# W5500_SCH.net
KiCad netlist of a schematic drawn in Altium Designer
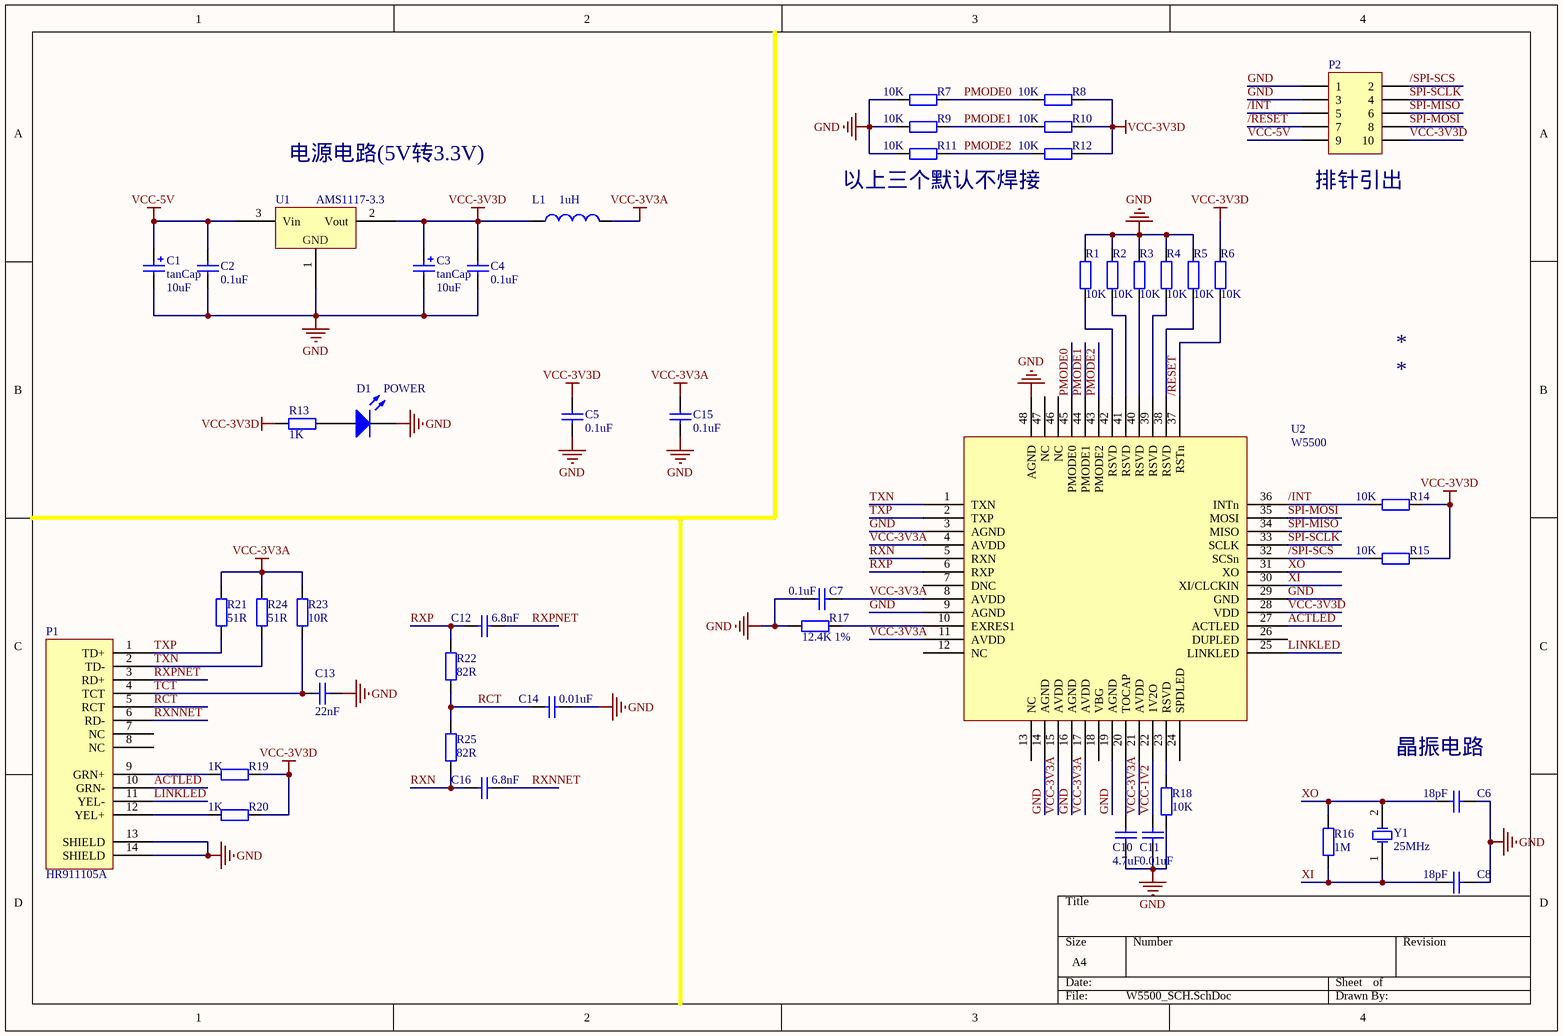
[diagram p0: W5500_SCH.SchDoc]

(export (version "E")
  (design (tool "Eeschema 10.0.6"))
  (components
    (comp (ref "C1")
      (value "tanCap")
      (footprint "C1206")
      (description "Polarized Capacitor (Axial)")
      (fields (field (name "ALTIUM_VALUE") "10uF") (field (name "PUBLISHER") "Altium Limited"))
      (libsource (lib "Miscellaneous Devices") (part "Cap Pol2"))
    )
    (comp (ref "C2")
      (value "0.1uF")
      (footprint "C0805")
      (description "Capacitor")
      (fields (field (name "Comment") "Cap") (field (name "PUBLISHER") "Altium Limited"))
      (libsource (lib "Miscellaneous Devices") (part "Cap"))
    )
    (comp (ref "C3")
      (value "tanCap")
      (footprint "C1206")
      (description "Polarized Capacitor (Axial)")
      (fields (field (name "ALTIUM_VALUE") "10uF") (field (name "PUBLISHER") "Altium Limited"))
      (libsource (lib "Miscellaneous Devices") (part "Cap Pol2"))
    )
    (comp (ref "C4")
      (value "0.1uF")
      (footprint "C0805")
      (description "Capacitor")
      (fields (field (name "Comment") "Cap") (field (name "PUBLISHER") "Altium Limited"))
      (libsource (lib "Miscellaneous Devices") (part "Cap"))
    )
    (comp (ref "C5")
      (value "0.1uF")
      (footprint "C0805")
      (description "Capacitor")
      (fields (field (name "Comment") "Cap") (field (name "PUBLISHER") "Altium Limited"))
      (libsource (lib "Miscellaneous Devices") (part "Cap"))
    )
    (comp (ref "C6")
      (value "18pF")
      (footprint "C0805")
      (description "Capacitor")
      (fields (field (name "Comment") "Cap") (field (name "PUBLISHER") "Altium Limited"))
      (libsource (lib "Miscellaneous Devices") (part "Cap"))
    )
    (comp (ref "C7")
      (value "0.1uF")
      (footprint "C0805")
      (description "Capacitor")
      (fields (field (name "Comment") "Cap") (field (name "PUBLISHER") "Altium Limited"))
      (libsource (lib "Miscellaneous Devices") (part "Cap"))
    )
    (comp (ref "C8")
      (value "18pF")
      (footprint "C0805")
      (description "Capacitor")
      (fields (field (name "Comment") "Cap") (field (name "PUBLISHER") "Altium Limited"))
      (libsource (lib "Miscellaneous Devices") (part "Cap"))
    )
    (comp (ref "C10")
      (value "4.7uF")
      (footprint "C0805")
      (description "Capacitor")
      (fields (field (name "Comment") "Cap") (field (name "PUBLISHER") "Altium Limited"))
      (libsource (lib "Miscellaneous Devices") (part "Cap"))
    )
    (comp (ref "C11")
      (value "0.01uF")
      (footprint "C0805")
      (description "Capacitor")
      (fields (field (name "Comment") "Cap") (field (name "PUBLISHER") "Altium Limited"))
      (libsource (lib "Miscellaneous Devices") (part "Cap"))
    )
    (comp (ref "C12")
      (value "6.8nF")
      (footprint "C0805")
      (description "Capacitor")
      (fields (field (name "Comment") "Cap") (field (name "PUBLISHER") "Altium Limited"))
      (libsource (lib "Miscellaneous Devices") (part "Cap"))
    )
    (comp (ref "C13")
      (value "22nF")
      (footprint "C0805")
      (description "Capacitor")
      (fields (field (name "Comment") "Cap") (field (name "PUBLISHER") "Altium Limited"))
      (libsource (lib "Miscellaneous Devices") (part "Cap"))
    )
    (comp (ref "C14")
      (value "0.01uF")
      (footprint "C0805")
      (description "Capacitor")
      (fields (field (name "Comment") "Cap") (field (name "PUBLISHER") "Altium Limited"))
      (libsource (lib "Miscellaneous Devices") (part "Cap"))
    )
    (comp (ref "C15")
      (value "0.1uF")
      (footprint "C0805")
      (description "Capacitor")
      (fields (field (name "Comment") "Cap") (field (name "PUBLISHER") "Altium Limited"))
      (libsource (lib "Miscellaneous Devices") (part "Cap"))
    )
    (comp (ref "C16")
      (value "6.8nF")
      (footprint "C0805")
      (description "Capacitor")
      (fields (field (name "Comment") "Cap") (field (name "PUBLISHER") "Altium Limited"))
      (libsource (lib "Miscellaneous Devices") (part "Cap"))
    )
    (comp (ref "D1")
      (value "POWER")
      (footprint "C0805")
      (description "Typical INFRARED GaAs LED")
      (fields (field (name "PUBLISHER") "Altium Limited"))
      (libsource (lib "Miscellaneous Devices") (part "LED0"))
    )
    (comp (ref "L1")
      (value "1uH")
      (footprint "C0805")
      (description "Inductor")
      (fields (field (name "PUBLISHER") "Altium Limited"))
      (libsource (lib "Miscellaneous Devices") (part "Inductor"))
    )
    (comp (ref "P1")
      (value "HR911105A")
      (footprint "HR911105A")
      (description "RJ45插座")
      (libsource (lib "W5500_SCH") (part "HR911105A"))
    )
    (comp (ref "P2")
      (value "排针引出")
      (footprint "HDR2X5")
      (description "Header, 5-Pin, Dual row")
      (fields (field (name "PUBLISHER") "Altium Limited"))
      (libsource (lib "Miscellaneous Connectors") (part "Header 5X2"))
    )
    (comp (ref "R1")
      (value "10K")
      (footprint "C0805")
      (description "Resistor")
      (fields (field (name "Comment") "Res2") (field (name "PUBLISHER") "Altium Limited"))
      (libsource (lib "Miscellaneous Devices") (part "Res2"))
    )
    (comp (ref "R2")
      (value "10K")
      (footprint "C0805")
      (description "Resistor")
      (fields (field (name "Comment") "Res2") (field (name "PUBLISHER") "Altium Limited"))
      (libsource (lib "Miscellaneous Devices") (part "Res2"))
    )
    (comp (ref "R3")
      (value "10K")
      (footprint "C0805")
      (description "Resistor")
      (fields (field (name "Comment") "Res2") (field (name "PUBLISHER") "Altium Limited"))
      (libsource (lib "Miscellaneous Devices") (part "Res2"))
    )
    (comp (ref "R4")
      (value "10K")
      (footprint "C0805")
      (description "Resistor")
      (fields (field (name "Comment") "Res2") (field (name "PUBLISHER") "Altium Limited"))
      (libsource (lib "Miscellaneous Devices") (part "Res2"))
    )
    (comp (ref "R5")
      (value "10K")
      (footprint "C0805")
      (description "Resistor")
      (fields (field (name "Comment") "Res2") (field (name "PUBLISHER") "Altium Limited"))
      (libsource (lib "Miscellaneous Devices") (part "Res2"))
    )
    (comp (ref "R6")
      (value "10K")
      (footprint "C0805")
      (description "Resistor")
      (fields (field (name "Comment") "Res2") (field (name "PUBLISHER") "Altium Limited"))
      (libsource (lib "Miscellaneous Devices") (part "Res2"))
    )
    (comp (ref "R7")
      (value "10K")
      (footprint "C0805")
      (description "Resistor")
      (fields (field (name "Comment") "Res2") (field (name "PUBLISHER") "Altium Limited"))
      (libsource (lib "") (part "Res2_1"))
    )
    (comp (ref "R8")
      (value "10K")
      (footprint "C0805")
      (description "Resistor")
      (fields (field (name "Comment") "Res2") (field (name "PUBLISHER") "Altium Limited"))
      (libsource (lib "") (part "Res2_1"))
    )
    (comp (ref "R9")
      (value "10K")
      (footprint "C0805")
      (description "Resistor")
      (fields (field (name "Comment") "Res2") (field (name "PUBLISHER") "Altium Limited"))
      (libsource (lib "") (part "Res2_1"))
    )
    (comp (ref "R10")
      (value "10K")
      (footprint "C0805")
      (description "Resistor")
      (fields (field (name "Comment") "Res2") (field (name "PUBLISHER") "Altium Limited"))
      (libsource (lib "") (part "Res2_1"))
    )
    (comp (ref "R11")
      (value "10K")
      (footprint "C0805")
      (description "Resistor")
      (fields (field (name "Comment") "Res2") (field (name "PUBLISHER") "Altium Limited"))
      (libsource (lib "") (part "Res2_1"))
    )
    (comp (ref "R12")
      (value "10K")
      (footprint "C0805")
      (description "Resistor")
      (fields (field (name "Comment") "Res2") (field (name "PUBLISHER") "Altium Limited"))
      (libsource (lib "") (part "Res2_1"))
    )
    (comp (ref "R13")
      (value "1K")
      (footprint "C0805")
      (description "Resistor")
      (fields (field (name "Comment") "Res2") (field (name "PUBLISHER") "Altium Limited"))
      (libsource (lib "") (part "Res2_2"))
    )
    (comp (ref "R14")
      (value "10K")
      (footprint "C0805")
      (description "Resistor")
      (fields (field (name "Comment") "Res2") (field (name "PUBLISHER") "Altium Limited"))
      (libsource (lib "") (part "Res2_1"))
    )
    (comp (ref "R15")
      (value "10K")
      (footprint "C0805")
      (description "Resistor")
      (fields (field (name "Comment") "Res2") (field (name "PUBLISHER") "Altium Limited"))
      (libsource (lib "") (part "Res2_1"))
    )
    (comp (ref "R16")
      (value "1M")
      (footprint "C0805")
      (description "Resistor")
      (fields (field (name "Comment") "Res2") (field (name "PUBLISHER") "Altium Limited"))
      (libsource (lib "Miscellaneous Devices") (part "Res2"))
    )
    (comp (ref "R17")
      (value "12.4K 1%")
      (footprint "C0805")
      (description "Resistor")
      (fields (field (name "Comment") "Res2") (field (name "PUBLISHER") "Altium Limited"))
      (libsource (lib "") (part "Res2_1"))
    )
    (comp (ref "R18")
      (value "10K")
      (footprint "C0805")
      (description "Resistor")
      (fields (field (name "Comment") "Res2") (field (name "PUBLISHER") "Altium Limited"))
      (libsource (lib "Miscellaneous Devices") (part "Res2"))
    )
    (comp (ref "R19")
      (value "1K")
      (footprint "C0805")
      (description "Resistor")
      (fields (field (name "Comment") "Res2") (field (name "PUBLISHER") "Altium Limited"))
      (libsource (lib "") (part "Res2_2"))
    )
    (comp (ref "R20")
      (value "1K")
      (footprint "C0805")
      (description "Resistor")
      (fields (field (name "Comment") "Res2") (field (name "PUBLISHER") "Altium Limited"))
      (libsource (lib "") (part "Res2_2"))
    )
    (comp (ref "R21")
      (value "51R")
      (footprint "C0805")
      (description "Resistor")
      (fields (field (name "Comment") "Res2") (field (name "PUBLISHER") "Altium Limited"))
      (libsource (lib "") (part "Res2_3"))
    )
    (comp (ref "R22")
      (value "82R")
      (footprint "C0805")
      (description "Resistor")
      (fields (field (name "Comment") "Res2") (field (name "PUBLISHER") "Altium Limited"))
      (libsource (lib "Miscellaneous Devices") (part "Res2"))
    )
    (comp (ref "R23")
      (value "10R")
      (footprint "C0805")
      (description "Resistor")
      (fields (field (name "Comment") "Res2") (field (name "PUBLISHER") "Altium Limited"))
      (libsource (lib "") (part "Res2_3"))
    )
    (comp (ref "R24")
      (value "51R")
      (footprint "C0805")
      (description "Resistor")
      (fields (field (name "Comment") "Res2") (field (name "PUBLISHER") "Altium Limited"))
      (libsource (lib "") (part "Res2_3"))
    )
    (comp (ref "R25")
      (value "82R")
      (footprint "C0805")
      (description "Resistor")
      (fields (field (name "Comment") "Res2") (field (name "PUBLISHER") "Altium Limited"))
      (libsource (lib "Miscellaneous Devices") (part "Res2"))
    )
    (comp (ref "U1")
      (value "AMS1117-3.3")
      (footprint "SOT223_M")
      (description "AMS1117-")
      (libsource (lib "qyh") (part "AMS1117"))
    )
    (comp (ref "U2")
      (value "W5500")
      (footprint "LQFP48")
      (description "W5500以太网芯片")
      (libsource (lib "W5500_SCH") (part "W5500"))
    )
    (comp (ref "Y1")
      (value "25MHz")
      (footprint "XTAL-HC49")
      (description "Crystal Oscillator")
      (fields (field (name "PUBLISHER") "Altium Limited"))
      (libsource (lib "Miscellaneous Devices") (part "XTAL"))
    )
  )
  (nets
    (net (code "1") (name "/ACTLED") (class "Default")
      (node (ref "P1") (pin "10") (pinfunction "GRN-_10") (pintype "passive"))
      (node (ref "U2") (pin "27") (pinfunction "ACTLED_27") (pintype "passive"))
    )
    (net (code "2") (name "/LINKLED") (class "Default")
      (node (ref "P1") (pin "11") (pinfunction "YEL-_11") (pintype "passive"))
      (node (ref "U2") (pin "25") (pinfunction "LINKLED_25") (pintype "passive"))
    )
    (net (code "3") (name "/PMODE0") (class "Default")
      (node (ref "R7") (pin "2") (pinfunction "2_2") (pintype "passive"))
      (node (ref "R8") (pin "1") (pinfunction "1_1") (pintype "passive"))
      (node (ref "U2") (pin "45") (pinfunction "PMODE0_45") (pintype "passive"))
    )
    (net (code "4") (name "/PMODE1") (class "Default")
      (node (ref "R10") (pin "1") (pinfunction "1_1") (pintype "passive"))
      (node (ref "R9") (pin "2") (pinfunction "2_2") (pintype "passive"))
      (node (ref "U2") (pin "44") (pinfunction "PMODE1_44") (pintype "passive"))
    )
    (net (code "5") (name "/PMODE2") (class "Default")
      (node (ref "R11") (pin "2") (pinfunction "2_2") (pintype "passive"))
      (node (ref "R12") (pin "1") (pinfunction "1_1") (pintype "passive"))
      (node (ref "U2") (pin "43") (pinfunction "PMODE2_43") (pintype "passive"))
    )
    (net (code "6") (name "/RCT") (class "Default")
      (node (ref "C14") (pin "2") (pinfunction "2_2") (pintype "passive"))
      (node (ref "P1") (pin "5") (pinfunction "RCT_5") (pintype "passive"))
      (node (ref "R22") (pin "1") (pinfunction "1_1") (pintype "passive"))
      (node (ref "R25") (pin "2") (pinfunction "2_2") (pintype "passive"))
    )
    (net (code "7") (name "/RXN") (class "Default")
      (node (ref "C16") (pin "2") (pinfunction "2_2") (pintype "passive"))
      (node (ref "R25") (pin "1") (pinfunction "1_1") (pintype "passive"))
      (node (ref "U2") (pin "5") (pinfunction "RXN_5") (pintype "passive"))
    )
    (net (code "8") (name "/RXNNET") (class "Default")
      (node (ref "C16") (pin "1") (pinfunction "1_1") (pintype "passive"))
      (node (ref "P1") (pin "6") (pinfunction "RD-_6") (pintype "passive"))
    )
    (net (code "9") (name "/RXP") (class "Default")
      (node (ref "C12") (pin "2") (pinfunction "2_2") (pintype "passive"))
      (node (ref "R22") (pin "2") (pinfunction "2_2") (pintype "passive"))
      (node (ref "U2") (pin "6") (pinfunction "RXP_6") (pintype "passive"))
    )
    (net (code "10") (name "/RXPNET") (class "Default")
      (node (ref "C12") (pin "1") (pinfunction "1_1") (pintype "passive"))
      (node (ref "P1") (pin "3") (pinfunction "RD+_3") (pintype "passive"))
    )
    (net (code "11") (name "/SPI-MISO") (class "Default")
      (node (ref "P2") (pin "6") (pinfunction "6_6") (pintype "passive"))
      (node (ref "U2") (pin "34") (pinfunction "MISO_34") (pintype "passive"))
    )
    (net (code "12") (name "/SPI-MOSI") (class "Default")
      (node (ref "P2") (pin "8") (pinfunction "8_8") (pintype "passive"))
      (node (ref "U2") (pin "35") (pinfunction "MOSI_35") (pintype "passive"))
    )
    (net (code "13") (name "/SPI-SCLK") (class "Default")
      (node (ref "P2") (pin "4") (pinfunction "4_4") (pintype "passive"))
      (node (ref "U2") (pin "33") (pinfunction "SCLK_33") (pintype "passive"))
    )
    (net (code "14") (name "/TCT") (class "Default")
      (node (ref "C13") (pin "1") (pinfunction "1_1") (pintype "passive"))
      (node (ref "P1") (pin "4") (pinfunction "TCT_4") (pintype "passive"))
      (node (ref "R23") (pin "2") (pinfunction "2_2") (pintype "passive"))
    )
    (net (code "15") (name "/TXN") (class "Default")
      (node (ref "P1") (pin "2") (pinfunction "TD-_2") (pintype "passive"))
      (node (ref "R24") (pin "2") (pinfunction "2_2") (pintype "passive"))
      (node (ref "U2") (pin "1") (pinfunction "TXN_1") (pintype "passive"))
    )
    (net (code "16") (name "/TXP") (class "Default")
      (node (ref "P1") (pin "1") (pinfunction "TD+_1") (pintype "passive"))
      (node (ref "R21") (pin "2") (pinfunction "2_2") (pintype "passive"))
      (node (ref "U2") (pin "2") (pinfunction "TXP_2") (pintype "passive"))
    )
    (net (code "17") (name "/VCC-1V2") (class "Default")
      (node (ref "C11") (pin "1") (pinfunction "1_1") (pintype "passive"))
      (node (ref "U2") (pin "22") (pinfunction "1V2O_22") (pintype "passive"))
    )
    (net (code "18") (name "/XI") (class "Default")
      (node (ref "C8") (pin "2") (pinfunction "2_2") (pintype "passive"))
      (node (ref "R16") (pin "1") (pinfunction "1_1") (pintype "passive"))
      (node (ref "U2") (pin "30") (pinfunction "XI/CLCKIN_30") (pintype "passive"))
      (node (ref "Y1") (pin "1") (pinfunction "OSC1_1") (pintype "passive"))
    )
    (net (code "19") (name "/XO") (class "Default")
      (node (ref "C6") (pin "2") (pinfunction "2_2") (pintype "passive"))
      (node (ref "R16") (pin "2") (pinfunction "2_2") (pintype "passive"))
      (node (ref "U2") (pin "31") (pinfunction "XO_31") (pintype "passive"))
      (node (ref "Y1") (pin "2") (pinfunction "OSC2_2") (pintype "passive"))
    )
    (net (code "20") (name "/{slash}INT") (class "Default")
      (node (ref "P2") (pin "5") (pinfunction "5_5") (pintype "passive"))
      (node (ref "R14") (pin "1") (pinfunction "1_1") (pintype "passive"))
      (node (ref "U2") (pin "36") (pinfunction "INTn_36") (pintype "passive"))
    )
    (net (code "21") (name "/{slash}RESET") (class "Default")
      (node (ref "P2") (pin "7") (pinfunction "7_7") (pintype "passive"))
      (node (ref "R6") (pin "1") (pinfunction "1_1") (pintype "passive"))
      (node (ref "U2") (pin "37") (pinfunction "RSTn_37") (pintype "passive"))
    )
    (net (code "22") (name "/{slash}SPI-SCS") (class "Default")
      (node (ref "P2") (pin "2") (pinfunction "2_2") (pintype "passive"))
      (node (ref "R15") (pin "1") (pinfunction "1_1") (pintype "passive"))
      (node (ref "U2") (pin "32") (pinfunction "SCSn_32") (pintype "passive"))
    )
    (net (code "23") (name "GND") (class "Default")
      (node (ref "C1") (pin "2") (pinfunction "2_2") (pintype "passive"))
      (node (ref "C10") (pin "2") (pinfunction "2_2") (pintype "passive"))
      (node (ref "C11") (pin "2") (pinfunction "2_2") (pintype "passive"))
      (node (ref "C13") (pin "2") (pinfunction "2_2") (pintype "passive"))
      (node (ref "C14") (pin "1") (pinfunction "1_1") (pintype "passive"))
      (node (ref "C15") (pin "1") (pinfunction "1_1") (pintype "passive"))
      (node (ref "C2") (pin "2") (pinfunction "2_2") (pintype "passive"))
      (node (ref "C3") (pin "2") (pinfunction "2_2") (pintype "passive"))
      (node (ref "C4") (pin "2") (pinfunction "2_2") (pintype "passive"))
      (node (ref "C5") (pin "2") (pinfunction "2_2") (pintype "passive"))
      (node (ref "C6") (pin "1") (pinfunction "1_1") (pintype "passive"))
      (node (ref "C7") (pin "2") (pinfunction "2_2") (pintype "passive"))
      (node (ref "C8") (pin "1") (pinfunction "1_1") (pintype "passive"))
      (node (ref "D1") (pin "2") (pinfunction "K_2") (pintype "passive"))
      (node (ref "P1") (pin "13") (pinfunction "SHIELD_13") (pintype "passive"))
      (node (ref "P1") (pin "14") (pinfunction "SHIELD_14") (pintype "passive"))
      (node (ref "P2") (pin "1") (pinfunction "1_1") (pintype "passive"))
      (node (ref "P2") (pin "3") (pinfunction "3_3") (pintype "passive"))
      (node (ref "R1") (pin "2") (pinfunction "2_2") (pintype "passive"))
      (node (ref "R11") (pin "1") (pinfunction "1_1") (pintype "passive"))
      (node (ref "R17") (pin "1") (pinfunction "1_1") (pintype "passive"))
      (node (ref "R18") (pin "1") (pinfunction "1_1") (pintype "passive"))
      (node (ref "R2") (pin "2") (pinfunction "2_2") (pintype "passive"))
      (node (ref "R3") (pin "2") (pinfunction "2_2") (pintype "passive"))
      (node (ref "R4") (pin "2") (pinfunction "2_2") (pintype "passive"))
      (node (ref "R5") (pin "2") (pinfunction "2_2") (pintype "passive"))
      (node (ref "R7") (pin "1") (pinfunction "1_1") (pintype "passive"))
      (node (ref "R9") (pin "1") (pinfunction "1_1") (pintype "passive"))
      (node (ref "U1") (pin "1") (pinfunction "GND_1") (pintype "passive"))
      (node (ref "U2") (pin "14") (pinfunction "AGND_14") (pintype "passive"))
      (node (ref "U2") (pin "16") (pinfunction "AGND_16") (pintype "passive"))
      (node (ref "U2") (pin "19") (pinfunction "AGND_19") (pintype "passive"))
      (node (ref "U2") (pin "29") (pinfunction "GND_29") (pintype "passive"))
      (node (ref "U2") (pin "3") (pinfunction "AGND_3") (pintype "passive"))
      (node (ref "U2") (pin "48") (pinfunction "AGND_48") (pintype "passive"))
      (node (ref "U2") (pin "9") (pinfunction "AGND_9") (pintype "passive"))
    )
    (net (code "24") (name "Net-(D1-A)") (class "Default")
      (node (ref "D1") (pin "1") (pinfunction "A_1") (pintype "passive"))
      (node (ref "R13") (pin "1") (pinfunction "1_1") (pintype "passive"))
    )
    (net (code "25") (name "Net-(P1-GRN+)") (class "Default")
      (node (ref "P1") (pin "9") (pinfunction "GRN+_9") (pintype "passive"))
      (node (ref "R19") (pin "2") (pinfunction "2_2") (pintype "passive"))
    )
    (net (code "26") (name "Net-(P1-YEL+)") (class "Default")
      (node (ref "P1") (pin "12") (pinfunction "YEL+_12") (pintype "passive"))
      (node (ref "R20") (pin "2") (pinfunction "2_2") (pintype "passive"))
    )
    (net (code "27") (name "Net-(R1-Pad1)") (class "Default")
      (node (ref "R1") (pin "1") (pinfunction "1_1") (pintype "passive"))
      (node (ref "U2") (pin "42") (pinfunction "RSVD_42") (pintype "passive"))
    )
    (net (code "28") (name "Net-(R2-Pad1)") (class "Default")
      (node (ref "R2") (pin "1") (pinfunction "1_1") (pintype "passive"))
      (node (ref "U2") (pin "41") (pinfunction "RSVD_41") (pintype "passive"))
    )
    (net (code "29") (name "Net-(R3-Pad1)") (class "Default")
      (node (ref "R3") (pin "1") (pinfunction "1_1") (pintype "passive"))
      (node (ref "U2") (pin "40") (pinfunction "RSVD_40") (pintype "passive"))
    )
    (net (code "30") (name "Net-(R4-Pad1)") (class "Default")
      (node (ref "R4") (pin "1") (pinfunction "1_1") (pintype "passive"))
      (node (ref "U2") (pin "39") (pinfunction "RSVD_39") (pintype "passive"))
    )
    (net (code "31") (name "Net-(R5-Pad1)") (class "Default")
      (node (ref "R5") (pin "1") (pinfunction "1_1") (pintype "passive"))
      (node (ref "U2") (pin "38") (pinfunction "RSVD_38") (pintype "passive"))
    )
    (net (code "32") (name "Net-(R18-Pad2)") (class "Default")
      (node (ref "R18") (pin "2") (pinfunction "2_2") (pintype "passive"))
      (node (ref "U2") (pin "23") (pinfunction "RSVD_23") (pintype "passive"))
    )
    (net (code "33") (name "Net-(U2-EXRES1)") (class "Default")
      (node (ref "R17") (pin "2") (pinfunction "2_2") (pintype "passive"))
      (node (ref "U2") (pin "10") (pinfunction "EXRES1_10") (pintype "passive"))
    )
    (net (code "34") (name "Net-(U2-TOCAP)") (class "Default")
      (node (ref "C10") (pin "1") (pinfunction "1_1") (pintype "passive"))
      (node (ref "U2") (pin "20") (pinfunction "TOCAP_20") (pintype "passive"))
    )
    (net (code "35") (name "VCC-3V3A") (class "Default")
      (node (ref "C15") (pin "2") (pinfunction "2_2") (pintype "passive"))
      (node (ref "C7") (pin "1") (pinfunction "1_1") (pintype "passive"))
      (node (ref "L1") (pin "2") (pinfunction "2_2") (pintype "passive"))
      (node (ref "R21") (pin "1") (pinfunction "1_1") (pintype "passive"))
      (node (ref "R23") (pin "1") (pinfunction "1_1") (pintype "passive"))
      (node (ref "R24") (pin "1") (pinfunction "1_1") (pintype "passive"))
      (node (ref "U2") (pin "11") (pinfunction "AVDD_11") (pintype "passive"))
      (node (ref "U2") (pin "15") (pinfunction "AVDD_15") (pintype "passive"))
      (node (ref "U2") (pin "17") (pinfunction "AVDD_17") (pintype "passive"))
      (node (ref "U2") (pin "21") (pinfunction "AVDD_21") (pintype "passive"))
      (node (ref "U2") (pin "4") (pinfunction "AVDD_4") (pintype "passive"))
      (node (ref "U2") (pin "8") (pinfunction "AVDD_8") (pintype "passive"))
    )
    (net (code "36") (name "VCC-3V3D") (class "Default")
      (node (ref "C3") (pin "1") (pinfunction "1_1") (pintype "passive"))
      (node (ref "C4") (pin "1") (pinfunction "1_1") (pintype "passive"))
      (node (ref "C5") (pin "1") (pinfunction "1_1") (pintype "passive"))
      (node (ref "L1") (pin "1") (pinfunction "1_1") (pintype "passive"))
      (node (ref "P2") (pin "10") (pinfunction "10_10") (pintype "passive"))
      (node (ref "R10") (pin "2") (pinfunction "2_2") (pintype "passive"))
      (node (ref "R12") (pin "2") (pinfunction "2_2") (pintype "passive"))
      (node (ref "R13") (pin "2") (pinfunction "2_2") (pintype "passive"))
      (node (ref "R14") (pin "2") (pinfunction "2_2") (pintype "passive"))
      (node (ref "R15") (pin "2") (pinfunction "2_2") (pintype "passive"))
      (node (ref "R19") (pin "1") (pinfunction "1_1") (pintype "passive"))
      (node (ref "R20") (pin "1") (pinfunction "1_1") (pintype "passive"))
      (node (ref "R6") (pin "2") (pinfunction "2_2") (pintype "passive"))
      (node (ref "R8") (pin "2") (pinfunction "2_2") (pintype "passive"))
      (node (ref "U1") (pin "2") (pinfunction "Vout_2") (pintype "passive"))
      (node (ref "U2") (pin "28") (pinfunction "VDD_28") (pintype "passive"))
    )
    (net (code "37") (name "VCC-5V") (class "Default")
      (node (ref "C1") (pin "1") (pinfunction "1_1") (pintype "passive"))
      (node (ref "C2") (pin "1") (pinfunction "1_1") (pintype "passive"))
      (node (ref "P2") (pin "9") (pinfunction "9_9") (pintype "passive"))
      (node (ref "U1") (pin "3") (pinfunction "Vin_3") (pintype "passive"))
    )
    (net (code "38") (name "unconnected-(P1-NC-Pad7)") (class "Default")
      (node (ref "P1") (pin "7") (pinfunction "NC_7") (pintype "passive"))
    )
    (net (code "39") (name "unconnected-(P1-NC-Pad8)") (class "Default")
      (node (ref "P1") (pin "8") (pinfunction "NC_8") (pintype "passive"))
    )
    (net (code "40") (name "unconnected-(U2-DNC-Pad7)") (class "Default")
      (node (ref "U2") (pin "7") (pinfunction "DNC_7") (pintype "passive"))
    )
    (net (code "41") (name "unconnected-(U2-DUPLED-Pad26)") (class "Default")
      (node (ref "U2") (pin "26") (pinfunction "DUPLED_26") (pintype "passive"))
    )
    (net (code "42") (name "unconnected-(U2-NC-Pad12)") (class "Default")
      (node (ref "U2") (pin "12") (pinfunction "NC_12") (pintype "passive"))
    )
    (net (code "43") (name "unconnected-(U2-NC-Pad13)") (class "Default")
      (node (ref "U2") (pin "13") (pinfunction "NC_13") (pintype "passive"))
    )
    (net (code "44") (name "unconnected-(U2-NC-Pad46)") (class "Default")
      (node (ref "U2") (pin "46") (pinfunction "NC_46") (pintype "passive"))
    )
    (net (code "45") (name "unconnected-(U2-NC-Pad47)") (class "Default")
      (node (ref "U2") (pin "47") (pinfunction "NC_47") (pintype "passive"))
    )
    (net (code "46") (name "unconnected-(U2-SPDLED-Pad24)") (class "Default")
      (node (ref "U2") (pin "24") (pinfunction "SPDLED_24") (pintype "passive"))
    )
    (net (code "47") (name "unconnected-(U2-VBG-Pad18)") (class "Default")
      (node (ref "U2") (pin "18") (pinfunction "VBG_18") (pintype "passive"))
    )
  )
)
